# 2364_ROM-el_v1_1.net
KiCad netlist of a schematic drawn in EAGLE
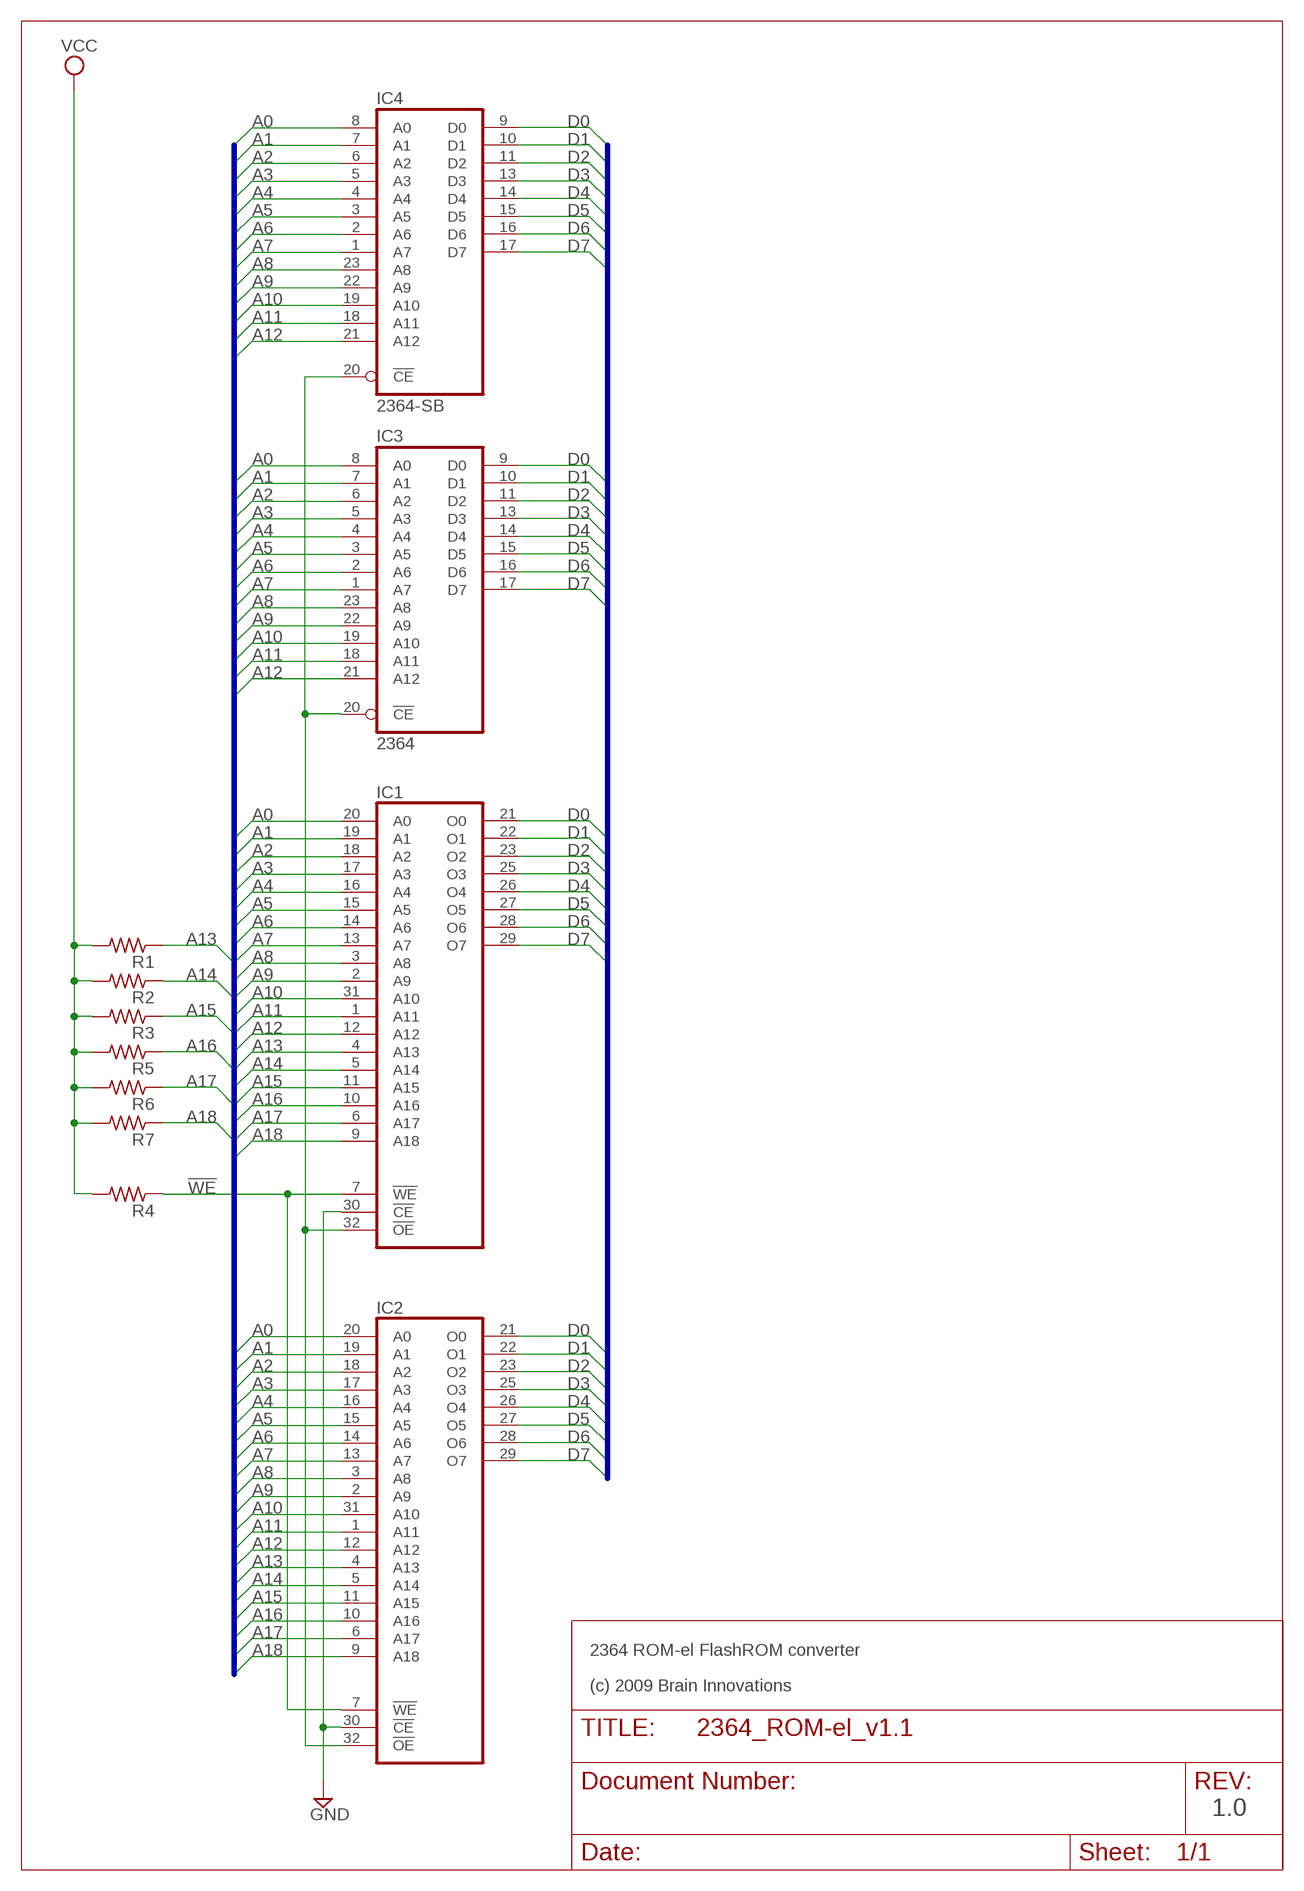
[diagram p0: schematic, sheet 1]

(export (version "E")
  (design (tool "Eeschema 10.0.6"))
  (components
    (comp (ref "IC1")
      (value "FLASH_RAM4096KB'T'")
      (footprint "eagle-import:TSOP32")
      (libsource (lib "eagle-import") (part "FLASH_RAM4096KB'T'"))
    )
    (comp (ref "IC2")
      (value "FLASH_RAM4096KB'V'")
      (footprint "eagle-import:VSOP32")
      (libsource (lib "eagle-import") (part "FLASH_RAM4096KB'V'"))
    )
    (comp (ref "IC3")
      (value "2364")
      (footprint "eagle-import:DIL24-ROUNDPAD")
      (libsource (lib "eagle-import") (part "2364-RP"))
    )
    (comp (ref "IC4")
      (value "2364-SB")
      (footprint "eagle-import:DIL24-SMD-REVERSE")
      (libsource (lib "eagle-import") (part "2364-SB"))
    )
    (comp (ref "R1")
      (value "R-US_R0805")
      (footprint "eagle-import:R0805")
      (libsource (lib "eagle-import") (part "R-US_R0805"))
    )
    (comp (ref "R2")
      (value "R-US_R0805")
      (footprint "eagle-import:R0805")
      (libsource (lib "eagle-import") (part "R-US_R0805"))
    )
    (comp (ref "R3")
      (value "R-US_R0805")
      (footprint "eagle-import:R0805")
      (libsource (lib "eagle-import") (part "R-US_R0805"))
    )
    (comp (ref "R4")
      (value "R-US_R0805")
      (footprint "eagle-import:R0805")
      (libsource (lib "eagle-import") (part "R-US_R0805"))
    )
    (comp (ref "R5")
      (value "R-US_R0805")
      (footprint "eagle-import:R0805")
      (libsource (lib "eagle-import") (part "R-US_R0805"))
    )
    (comp (ref "R6")
      (value "R-US_R0805")
      (footprint "eagle-import:R0805")
      (libsource (lib "eagle-import") (part "R-US_R0805"))
    )
    (comp (ref "R7")
      (value "R-US_R0805")
      (footprint "eagle-import:R0805")
      (libsource (lib "eagle-import") (part "R-US_R0805"))
    )
  )
  (nets
    (net (code "1") (name "/A0") (class "Default")
      (node (ref "IC1") (pin "20") (pinfunction "A0_20") (pintype "input"))
      (node (ref "IC2") (pin "20") (pinfunction "A0_20") (pintype "input"))
      (node (ref "IC3") (pin "8") (pinfunction "A0_8") (pintype "bidirectional"))
      (node (ref "IC4") (pin "8") (pinfunction "A0_8") (pintype "bidirectional"))
    )
    (net (code "2") (name "/A1") (class "Default")
      (node (ref "IC1") (pin "19") (pinfunction "A1_19") (pintype "input"))
      (node (ref "IC2") (pin "19") (pinfunction "A1_19") (pintype "input"))
      (node (ref "IC3") (pin "7") (pinfunction "A1_7") (pintype "bidirectional"))
      (node (ref "IC4") (pin "7") (pinfunction "A1_7") (pintype "bidirectional"))
    )
    (net (code "3") (name "/A2") (class "Default")
      (node (ref "IC1") (pin "18") (pinfunction "A2_18") (pintype "input"))
      (node (ref "IC2") (pin "18") (pinfunction "A2_18") (pintype "input"))
      (node (ref "IC3") (pin "6") (pinfunction "A2_6") (pintype "bidirectional"))
      (node (ref "IC4") (pin "6") (pinfunction "A2_6") (pintype "bidirectional"))
    )
    (net (code "4") (name "/A3") (class "Default")
      (node (ref "IC1") (pin "17") (pinfunction "A3_17") (pintype "input"))
      (node (ref "IC2") (pin "17") (pinfunction "A3_17") (pintype "input"))
      (node (ref "IC3") (pin "5") (pinfunction "A3_5") (pintype "bidirectional"))
      (node (ref "IC4") (pin "5") (pinfunction "A3_5") (pintype "bidirectional"))
    )
    (net (code "5") (name "/A4") (class "Default")
      (node (ref "IC1") (pin "16") (pinfunction "A4_16") (pintype "input"))
      (node (ref "IC2") (pin "16") (pinfunction "A4_16") (pintype "input"))
      (node (ref "IC3") (pin "4") (pinfunction "A4_4") (pintype "bidirectional"))
      (node (ref "IC4") (pin "4") (pinfunction "A4_4") (pintype "bidirectional"))
    )
    (net (code "6") (name "/A5") (class "Default")
      (node (ref "IC1") (pin "15") (pinfunction "A5_15") (pintype "input"))
      (node (ref "IC2") (pin "15") (pinfunction "A5_15") (pintype "input"))
      (node (ref "IC3") (pin "3") (pinfunction "A5_3") (pintype "bidirectional"))
      (node (ref "IC4") (pin "3") (pinfunction "A5_3") (pintype "bidirectional"))
    )
    (net (code "7") (name "/A6") (class "Default")
      (node (ref "IC1") (pin "14") (pinfunction "A6_14") (pintype "input"))
      (node (ref "IC2") (pin "14") (pinfunction "A6_14") (pintype "input"))
      (node (ref "IC3") (pin "2") (pinfunction "A6_2") (pintype "bidirectional"))
      (node (ref "IC4") (pin "2") (pinfunction "A6_2") (pintype "bidirectional"))
    )
    (net (code "8") (name "/A7") (class "Default")
      (node (ref "IC1") (pin "13") (pinfunction "A7_13") (pintype "input"))
      (node (ref "IC2") (pin "13") (pinfunction "A7_13") (pintype "input"))
      (node (ref "IC3") (pin "1") (pinfunction "A7_1") (pintype "bidirectional"))
      (node (ref "IC4") (pin "1") (pinfunction "A7_1") (pintype "bidirectional"))
    )
    (net (code "9") (name "/A8") (class "Default")
      (node (ref "IC1") (pin "3") (pinfunction "A8_3") (pintype "input"))
      (node (ref "IC2") (pin "3") (pinfunction "A8_3") (pintype "input"))
      (node (ref "IC3") (pin "23") (pinfunction "A8_23") (pintype "bidirectional"))
      (node (ref "IC4") (pin "23") (pinfunction "A8_23") (pintype "bidirectional"))
    )
    (net (code "10") (name "/A9") (class "Default")
      (node (ref "IC1") (pin "2") (pinfunction "A9_2") (pintype "input"))
      (node (ref "IC2") (pin "2") (pinfunction "A9_2") (pintype "input"))
      (node (ref "IC3") (pin "22") (pinfunction "A9_22") (pintype "bidirectional"))
      (node (ref "IC4") (pin "22") (pinfunction "A9_22") (pintype "bidirectional"))
    )
    (net (code "11") (name "/A10") (class "Default")
      (node (ref "IC1") (pin "31") (pinfunction "A10_31") (pintype "input"))
      (node (ref "IC2") (pin "31") (pinfunction "A10_31") (pintype "input"))
      (node (ref "IC3") (pin "19") (pinfunction "A10_19") (pintype "bidirectional"))
      (node (ref "IC4") (pin "19") (pinfunction "A10_19") (pintype "bidirectional"))
    )
    (net (code "12") (name "/A11") (class "Default")
      (node (ref "IC1") (pin "1") (pinfunction "A11_1") (pintype "input"))
      (node (ref "IC2") (pin "1") (pinfunction "A11_1") (pintype "input"))
      (node (ref "IC3") (pin "18") (pinfunction "A11_18") (pintype "bidirectional"))
      (node (ref "IC4") (pin "18") (pinfunction "A11_18") (pintype "bidirectional"))
    )
    (net (code "13") (name "/A12") (class "Default")
      (node (ref "IC1") (pin "12") (pinfunction "A12_12") (pintype "input"))
      (node (ref "IC2") (pin "12") (pinfunction "A12_12") (pintype "input"))
      (node (ref "IC3") (pin "21") (pinfunction "A12_21") (pintype "bidirectional"))
      (node (ref "IC4") (pin "21") (pinfunction "A12_21") (pintype "bidirectional"))
    )
    (net (code "14") (name "/A13") (class "Default")
      (node (ref "IC1") (pin "4") (pinfunction "A13_4") (pintype "input"))
      (node (ref "IC2") (pin "4") (pinfunction "A13_4") (pintype "input"))
      (node (ref "R1") (pin "1") (pinfunction "1_1") (pintype "passive"))
    )
    (net (code "15") (name "/A14") (class "Default")
      (node (ref "IC1") (pin "5") (pinfunction "A14_5") (pintype "input"))
      (node (ref "IC2") (pin "5") (pinfunction "A14_5") (pintype "input"))
      (node (ref "R2") (pin "1") (pinfunction "1_1") (pintype "passive"))
    )
    (net (code "16") (name "/A15") (class "Default")
      (node (ref "IC1") (pin "11") (pinfunction "A15_11") (pintype "input"))
      (node (ref "IC2") (pin "11") (pinfunction "A15_11") (pintype "input"))
      (node (ref "R3") (pin "1") (pinfunction "1_1") (pintype "passive"))
    )
    (net (code "17") (name "/A16") (class "Default")
      (node (ref "IC1") (pin "10") (pinfunction "A16_10") (pintype "input"))
      (node (ref "IC2") (pin "10") (pinfunction "A16_10") (pintype "input"))
      (node (ref "R5") (pin "1") (pinfunction "1_1") (pintype "passive"))
    )
    (net (code "18") (name "/A17") (class "Default")
      (node (ref "IC1") (pin "6") (pinfunction "A17_6") (pintype "input"))
      (node (ref "IC2") (pin "6") (pinfunction "A17_6") (pintype "input"))
      (node (ref "R6") (pin "1") (pinfunction "1_1") (pintype "passive"))
    )
    (net (code "19") (name "/A18") (class "Default")
      (node (ref "IC1") (pin "9") (pinfunction "A18_9") (pintype "input"))
      (node (ref "IC2") (pin "9") (pinfunction "A18_9") (pintype "input"))
      (node (ref "R7") (pin "1") (pinfunction "1_1") (pintype "passive"))
    )
    (net (code "20") (name "/D0") (class "Default")
      (node (ref "IC1") (pin "21") (pinfunction "O0_21") (pintype "tri_state"))
      (node (ref "IC2") (pin "21") (pinfunction "O0_21") (pintype "tri_state"))
      (node (ref "IC3") (pin "9") (pinfunction "D0_9") (pintype "tri_state"))
      (node (ref "IC4") (pin "9") (pinfunction "D0_9") (pintype "tri_state"))
    )
    (net (code "21") (name "/D1") (class "Default")
      (node (ref "IC1") (pin "22") (pinfunction "O1_22") (pintype "tri_state"))
      (node (ref "IC2") (pin "22") (pinfunction "O1_22") (pintype "tri_state"))
      (node (ref "IC3") (pin "10") (pinfunction "D1_10") (pintype "tri_state"))
      (node (ref "IC4") (pin "10") (pinfunction "D1_10") (pintype "tri_state"))
    )
    (net (code "22") (name "/D2") (class "Default")
      (node (ref "IC1") (pin "23") (pinfunction "O2_23") (pintype "tri_state"))
      (node (ref "IC2") (pin "23") (pinfunction "O2_23") (pintype "tri_state"))
      (node (ref "IC3") (pin "11") (pinfunction "D2_11") (pintype "tri_state"))
      (node (ref "IC4") (pin "11") (pinfunction "D2_11") (pintype "tri_state"))
    )
    (net (code "23") (name "/D3") (class "Default")
      (node (ref "IC1") (pin "25") (pinfunction "O3_25") (pintype "tri_state"))
      (node (ref "IC2") (pin "25") (pinfunction "O3_25") (pintype "tri_state"))
      (node (ref "IC3") (pin "13") (pinfunction "D3_13") (pintype "tri_state"))
      (node (ref "IC4") (pin "13") (pinfunction "D3_13") (pintype "tri_state"))
    )
    (net (code "24") (name "/D4") (class "Default")
      (node (ref "IC1") (pin "26") (pinfunction "O4_26") (pintype "tri_state"))
      (node (ref "IC2") (pin "26") (pinfunction "O4_26") (pintype "tri_state"))
      (node (ref "IC3") (pin "14") (pinfunction "D4_14") (pintype "tri_state"))
      (node (ref "IC4") (pin "14") (pinfunction "D4_14") (pintype "tri_state"))
    )
    (net (code "25") (name "/D5") (class "Default")
      (node (ref "IC1") (pin "27") (pinfunction "O5_27") (pintype "tri_state"))
      (node (ref "IC2") (pin "27") (pinfunction "O5_27") (pintype "tri_state"))
      (node (ref "IC3") (pin "15") (pinfunction "D5_15") (pintype "tri_state"))
      (node (ref "IC4") (pin "15") (pinfunction "D5_15") (pintype "tri_state"))
    )
    (net (code "26") (name "/D6") (class "Default")
      (node (ref "IC1") (pin "28") (pinfunction "O6_28") (pintype "tri_state"))
      (node (ref "IC2") (pin "28") (pinfunction "O6_28") (pintype "tri_state"))
      (node (ref "IC3") (pin "16") (pinfunction "D6_16") (pintype "tri_state"))
      (node (ref "IC4") (pin "16") (pinfunction "D6_16") (pintype "tri_state"))
    )
    (net (code "27") (name "/D7") (class "Default")
      (node (ref "IC1") (pin "29") (pinfunction "O7_29") (pintype "tri_state"))
      (node (ref "IC2") (pin "29") (pinfunction "O7_29") (pintype "tri_state"))
      (node (ref "IC3") (pin "17") (pinfunction "D7_17") (pintype "tri_state"))
      (node (ref "IC4") (pin "17") (pinfunction "D7_17") (pintype "tri_state"))
    )
    (net (code "28") (name "/~{WE}") (class "Default")
      (node (ref "IC1") (pin "7") (pinfunction "~{WE}_7") (pintype "input"))
      (node (ref "IC2") (pin "7") (pinfunction "~{WE}_7") (pintype "input"))
      (node (ref "R4") (pin "1") (pinfunction "1_1") (pintype "passive"))
    )
    (net (code "29") (name "GND") (class "Default")
      (node (ref "IC1") (pin "30") (pinfunction "~{CE}_30") (pintype "input"))
      (node (ref "IC2") (pin "30") (pinfunction "~{CE}_30") (pintype "input"))
    )
    (net (code "30") (name "Net-(IC1A-~{OE})") (class "Default")
      (node (ref "IC1") (pin "32") (pinfunction "~{OE}_32") (pintype "input"))
      (node (ref "IC2") (pin "32") (pinfunction "~{OE}_32") (pintype "input"))
      (node (ref "IC3") (pin "20") (pinfunction "~{CE}_20") (pintype "input"))
      (node (ref "IC4") (pin "20") (pinfunction "~{CE}_20") (pintype "input"))
    )
    (net (code "31") (name "VCC") (class "Default")
      (node (ref "R1") (pin "2") (pinfunction "2_2") (pintype "passive"))
      (node (ref "R2") (pin "2") (pinfunction "2_2") (pintype "passive"))
      (node (ref "R3") (pin "2") (pinfunction "2_2") (pintype "passive"))
      (node (ref "R4") (pin "2") (pinfunction "2_2") (pintype "passive"))
      (node (ref "R5") (pin "2") (pinfunction "2_2") (pintype "passive"))
      (node (ref "R6") (pin "2") (pinfunction "2_2") (pintype "passive"))
      (node (ref "R7") (pin "2") (pinfunction "2_2") (pintype "passive"))
    )
  )
)
